# P1_1.net
KiCad netlist of a schematic drawn in Altium Designer
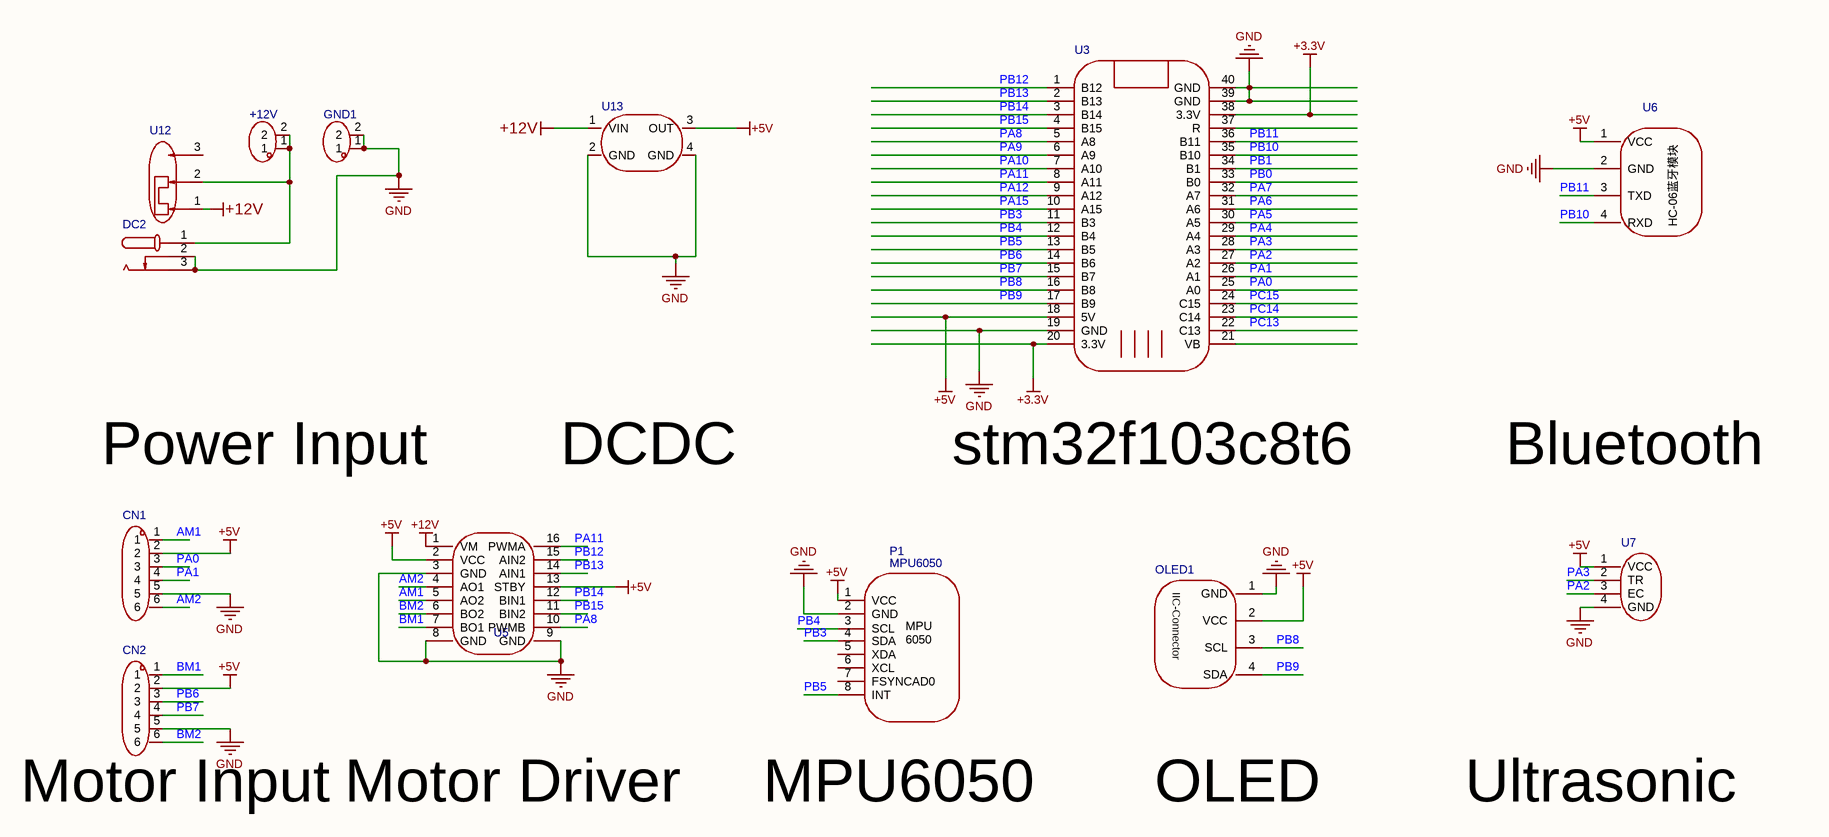
[diagram p0: P1_1.schdoc]

(export (version "E")
  (design (tool "Eeschema 10.0.6"))
  (components
    (comp (ref "+12V")
      (value "~")
      (footprint "HDR-TH_2P-P2.54-V")
      (description "2.54 1*2P 直排针 0.8u镀金 PBT RoHS,针长3*6mm")
      (fields
        (field (name "MANUFACTURER") "Nextron(台湾正凌)")
        (field (name "MANUFACTURERPART") "Z-211-0211-0021-001")
      )
      (libsource (lib "altium-import") (part "root_2_排针2P_"))
    )
    (comp (ref "CN1")
      (value "PH2.0-6P")
      (footprint "PH2.0-6P 直针端子座")
      (fields (field (name "MANUFACTURER") "CAX(创都)") (field (name "MANUFACTURERPART") "PH2.0-4P"))
      (libsource (lib "altium-import") (part "root_0_PH2.0-6P_"))
    )
    (comp (ref "CN2")
      (value "PH2.0-6P")
      (footprint "PH2.0-6P 直针端子座")
      (fields (field (name "MANUFACTURER") "CAX(创都)") (field (name "MANUFACTURERPART") "PH2.0-4P"))
      (libsource (lib "altium-import") (part "root_0_PH2.0-6P_"))
    )
    (comp (ref "DC2")
      (value "~")
      (footprint "DC-IN-TH_KH-DC-005-2.5")
      (description "连接器类型:DC电源插座;安装方式:弯插;触点内径:-;触点外径:6.4mm;额定电流:1A;额定电压:30V;工作温度范围:-25~+70;")
      (fields (field (name "MANUFACTURER") "kinghelm(金航标)") (field (name "MANUFACTURERPART") "KH-DC-005-2.5"))
      (libsource (lib "altium-import") (part "root_0_KH-DC-005-2.5_"))
    )
    (comp (ref "GND1")
      (value "~")
      (footprint "HDR-TH_2P-P2.54-V")
      (description "2.54 1*2P 直排针 0.8u镀金 PBT RoHS,针长3*6mm")
      (fields
        (field (name "MANUFACTURER") "Nextron(台湾正凌)")
        (field (name "MANUFACTURERPART") "Z-211-0211-0021-001")
      )
      (libsource (lib "altium-import") (part "root_2_排针2P_"))
    )
    (comp (ref "OLED1")
      (value "~")
      (footprint "0.96OLED_4P")
      (fields (field (name "MANUFACTURERPART") "0.96OLED_4P_MODULE_JX"))
      (libsource (lib "altium-import") (part "root_0_0.96OLED_4P_"))
    )
    (comp (ref "P1")
      (value "MPU6050")
      (footprint "MPU6050")
      (libsource (lib "altium-import") (part "root_0_MPU6050_"))
    )
    (comp (ref "U3")
      (value "~")
      (footprint "STM32F103C8T6核心板")
      (libsource (lib "altium-import") (part "root_0_stm32f103c8t6最小系统板_"))
    )
    (comp (ref "U5")
      (value "~")
      (footprint "TB6612FNG Module - 8pin x 2")
      (libsource (lib "altium-import") (part "root_0_TB6612FNG模块_"))
    )
    (comp (ref "U6")
      (value "~")
      (footprint "DIP-1X4P2.54（HC-06蓝牙模块）")
      (libsource (lib "altium-import") (part "root_0_蓝牙模块HC-06_"))
    )
    (comp (ref "U7")
      (value "~")
      (footprint "排母-4P")
      (libsource (lib "altium-import") (part "root_0_HC-SR04_1_"))
    )
    (comp (ref "U12")
      (value "SS-12D10-G5")
      (footprint "SW-TH_SS-12D10-G050")
      (description "电路结构:单刀双掷;安装方式:直插;开关颜色:黑色;滑钮形状:矩形柱状;引脚样式:PC引脚;开关长度:12.7mm;开关宽度:6.7mm;开关高度:11.3mm;")
      (fields (field (name "MANUFACTURER") "DEALON(德艺隆)"))
      (libsource (lib "altium-import") (part "root_1_SS-12D10-G5_"))
    )
    (comp (ref "U13")
      (value "~")
      (footprint "MP1584模块")
      (libsource (lib "altium-import") (part "root_0_MP1584模块_"))
    )
  )
  (nets
    (net (code "1") (name "+3.3V") (class "Default")
      (node (ref "U3") (pin "20") (pinfunction "3.3V_20") (pintype "passive"))
      (node (ref "U3") (pin "38") (pinfunction "3.3V_38") (pintype "passive"))
    )
    (net (code "2") (name "+5V") (class "Default")
      (node (ref "CN1") (pin "2") (pinfunction "2_2") (pintype "passive"))
      (node (ref "CN2") (pin "2") (pinfunction "2_2") (pintype "passive"))
      (node (ref "OLED1") (pin "2") (pinfunction "VCC_2") (pintype "passive"))
      (node (ref "P1") (pin "1") (pinfunction "VCC_1") (pintype "passive"))
      (node (ref "U13") (pin "3") (pinfunction "OUT_3") (pintype "passive"))
      (node (ref "U3") (pin "18") (pinfunction "5V_18") (pintype "passive"))
      (node (ref "U5") (pin "13") (pinfunction "STBY_13") (pintype "passive"))
      (node (ref "U5") (pin "2") (pinfunction "VCC_2") (pintype "passive"))
      (node (ref "U6") (pin "1") (pinfunction "VCC_1") (pintype "passive"))
      (node (ref "U7") (pin "1") (pinfunction "VCC_1") (pintype "passive"))
    )
    (net (code "3") (name "+12V") (class "Default")
      (node (ref "U12") (pin "1") (pinfunction "1_1") (pintype "passive"))
      (node (ref "U13") (pin "1") (pinfunction "VIN_1") (pintype "passive"))
      (node (ref "U5") (pin "1") (pinfunction "VM_1") (pintype "passive"))
    )
    (net (code "4") (name "/AM1") (class "Default")
      (node (ref "CN1") (pin "1") (pinfunction "1_1") (pintype "passive"))
      (node (ref "U5") (pin "5") (pinfunction "AO2_5") (pintype "passive"))
    )
    (net (code "5") (name "/AM2") (class "Default")
      (node (ref "CN1") (pin "6") (pinfunction "6_6") (pintype "passive"))
      (node (ref "U5") (pin "4") (pinfunction "AO1_4") (pintype "passive"))
    )
    (net (code "6") (name "/BM1") (class "Default")
      (node (ref "CN2") (pin "1") (pinfunction "1_1") (pintype "passive"))
      (node (ref "U5") (pin "7") (pinfunction "BO1_7") (pintype "passive"))
    )
    (net (code "7") (name "/BM2") (class "Default")
      (node (ref "CN2") (pin "6") (pinfunction "6_6") (pintype "passive"))
      (node (ref "U5") (pin "6") (pinfunction "BO2_6") (pintype "passive"))
    )
    (net (code "8") (name "/PA0") (class "Default")
      (node (ref "CN1") (pin "3") (pinfunction "3_3") (pintype "passive"))
      (node (ref "U3") (pin "25") (pinfunction "A0_25") (pintype "passive"))
    )
    (net (code "9") (name "/PA1") (class "Default")
      (node (ref "CN1") (pin "4") (pinfunction "4_4") (pintype "passive"))
      (node (ref "U3") (pin "26") (pinfunction "A1_26") (pintype "passive"))
    )
    (net (code "10") (name "/PA2") (class "Default")
      (node (ref "U3") (pin "27") (pinfunction "A2_27") (pintype "passive"))
      (node (ref "U7") (pin "3") (pinfunction "EC_3") (pintype "passive"))
    )
    (net (code "11") (name "/PA3") (class "Default")
      (node (ref "U3") (pin "28") (pinfunction "A3_28") (pintype "passive"))
      (node (ref "U7") (pin "2") (pinfunction "TR_2") (pintype "passive"))
    )
    (net (code "12") (name "/PA4") (class "Default")
      (node (ref "U3") (pin "29") (pinfunction "A4_29") (pintype "passive"))
    )
    (net (code "13") (name "/PA5") (class "Default")
      (node (ref "U3") (pin "30") (pinfunction "A5_30") (pintype "passive"))
    )
    (net (code "14") (name "/PA6") (class "Default")
      (node (ref "U3") (pin "31") (pinfunction "A6_31") (pintype "passive"))
    )
    (net (code "15") (name "/PA7") (class "Default")
      (node (ref "U3") (pin "32") (pinfunction "A7_32") (pintype "passive"))
    )
    (net (code "16") (name "/PA8") (class "Default")
      (node (ref "U3") (pin "5") (pinfunction "A8_5") (pintype "passive"))
      (node (ref "U5") (pin "10") (pinfunction "PWMB_10") (pintype "passive"))
    )
    (net (code "17") (name "/PA9") (class "Default")
      (node (ref "U3") (pin "6") (pinfunction "A9_6") (pintype "passive"))
    )
    (net (code "18") (name "/PA10") (class "Default")
      (node (ref "U3") (pin "7") (pinfunction "A10_7") (pintype "passive"))
    )
    (net (code "19") (name "/PA11") (class "Default")
      (node (ref "U3") (pin "8") (pinfunction "A11_8") (pintype "passive"))
      (node (ref "U5") (pin "16") (pinfunction "PWMA_16") (pintype "passive"))
    )
    (net (code "20") (name "/PA12") (class "Default")
      (node (ref "U3") (pin "9") (pinfunction "A12_9") (pintype "passive"))
    )
    (net (code "21") (name "/PA15") (class "Default")
      (node (ref "U3") (pin "10") (pinfunction "A15_10") (pintype "passive"))
    )
    (net (code "22") (name "/PB0") (class "Default")
      (node (ref "U3") (pin "33") (pinfunction "B0_33") (pintype "passive"))
    )
    (net (code "23") (name "/PB1") (class "Default")
      (node (ref "U3") (pin "34") (pinfunction "B1_34") (pintype "passive"))
    )
    (net (code "24") (name "/PB3") (class "Default")
      (node (ref "P1") (pin "4") (pinfunction "SDA_4") (pintype "passive"))
      (node (ref "U3") (pin "11") (pinfunction "B3_11") (pintype "passive"))
    )
    (net (code "25") (name "/PB4") (class "Default")
      (node (ref "P1") (pin "3") (pinfunction "SCL_3") (pintype "passive"))
      (node (ref "U3") (pin "12") (pinfunction "B4_12") (pintype "passive"))
    )
    (net (code "26") (name "/PB5") (class "Default")
      (node (ref "P1") (pin "8") (pinfunction "INT_8") (pintype "passive"))
      (node (ref "U3") (pin "13") (pinfunction "B5_13") (pintype "passive"))
    )
    (net (code "27") (name "/PB6") (class "Default")
      (node (ref "CN2") (pin "3") (pinfunction "3_3") (pintype "passive"))
      (node (ref "U3") (pin "14") (pinfunction "B6_14") (pintype "passive"))
    )
    (net (code "28") (name "/PB7") (class "Default")
      (node (ref "CN2") (pin "4") (pinfunction "4_4") (pintype "passive"))
      (node (ref "U3") (pin "15") (pinfunction "B7_15") (pintype "passive"))
    )
    (net (code "29") (name "/PB8") (class "Default")
      (node (ref "OLED1") (pin "3") (pinfunction "SCL_3") (pintype "passive"))
      (node (ref "U3") (pin "16") (pinfunction "B8_16") (pintype "passive"))
    )
    (net (code "30") (name "/PB9") (class "Default")
      (node (ref "OLED1") (pin "4") (pinfunction "SDA_4") (pintype "passive"))
      (node (ref "U3") (pin "17") (pinfunction "B9_17") (pintype "passive"))
    )
    (net (code "31") (name "/PB10") (class "Default")
      (node (ref "U3") (pin "35") (pinfunction "B10_35") (pintype "passive"))
      (node (ref "U6") (pin "4") (pinfunction "RXD_4") (pintype "passive"))
    )
    (net (code "32") (name "/PB11") (class "Default")
      (node (ref "U3") (pin "36") (pinfunction "B11_36") (pintype "passive"))
      (node (ref "U6") (pin "3") (pinfunction "TXD_3") (pintype "passive"))
    )
    (net (code "33") (name "/PB12") (class "Default")
      (node (ref "U3") (pin "1") (pinfunction "B12_1") (pintype "passive"))
      (node (ref "U5") (pin "15") (pinfunction "AIN2_15") (pintype "passive"))
    )
    (net (code "34") (name "/PB13") (class "Default")
      (node (ref "U3") (pin "2") (pinfunction "B13_2") (pintype "passive"))
      (node (ref "U5") (pin "14") (pinfunction "AIN1_14") (pintype "passive"))
    )
    (net (code "35") (name "/PB14") (class "Default")
      (node (ref "U3") (pin "3") (pinfunction "B14_3") (pintype "passive"))
      (node (ref "U5") (pin "12") (pinfunction "BIN1_12") (pintype "passive"))
    )
    (net (code "36") (name "/PB15") (class "Default")
      (node (ref "U3") (pin "4") (pinfunction "B15_4") (pintype "passive"))
      (node (ref "U5") (pin "11") (pinfunction "BIN2_11") (pintype "passive"))
    )
    (net (code "37") (name "/PC13") (class "Default")
      (node (ref "U3") (pin "22") (pinfunction "C13_22") (pintype "passive"))
    )
    (net (code "38") (name "/PC14") (class "Default")
      (node (ref "U3") (pin "23") (pinfunction "C14_23") (pintype "passive"))
    )
    (net (code "39") (name "/PC15") (class "Default")
      (node (ref "U3") (pin "24") (pinfunction "C15_24") (pintype "passive"))
    )
    (net (code "40") (name "GND") (class "Default")
      (node (ref "CN1") (pin "5") (pinfunction "5_5") (pintype "passive"))
      (node (ref "CN2") (pin "5") (pinfunction "5_5") (pintype "passive"))
      (node (ref "DC2") (pin "2") (pinfunction "2_2") (pintype "passive"))
      (node (ref "DC2") (pin "3") (pinfunction "3_3") (pintype "passive"))
      (node (ref "GND1") (pin "1") (pinfunction "1_1") (pintype "passive"))
      (node (ref "GND1") (pin "2") (pinfunction "2_2") (pintype "passive"))
      (node (ref "OLED1") (pin "1") (pinfunction "GND_1") (pintype "passive"))
      (node (ref "P1") (pin "2") (pinfunction "GND_2") (pintype "passive"))
      (node (ref "U13") (pin "2") (pinfunction "GND_2") (pintype "passive"))
      (node (ref "U13") (pin "4") (pinfunction "GND_4") (pintype "passive"))
      (node (ref "U3") (pin "19") (pinfunction "GND_19") (pintype "passive"))
      (node (ref "U3") (pin "39") (pinfunction "GND_39") (pintype "passive"))
      (node (ref "U3") (pin "40") (pinfunction "GND_40") (pintype "passive"))
      (node (ref "U5") (pin "3") (pinfunction "GND_3") (pintype "passive"))
      (node (ref "U5") (pin "8") (pinfunction "GND_8") (pintype "passive"))
      (node (ref "U5") (pin "9") (pinfunction "GND_9") (pintype "passive"))
      (node (ref "U6") (pin "2") (pinfunction "GND_2") (pintype "passive"))
      (node (ref "U7") (pin "4") (pinfunction "GND_4") (pintype "passive"))
    )
    (net (code "41") (name "Net-(+12V-Pad1)") (class "Default")
      (node (ref "+12V") (pin "1") (pinfunction "1_1") (pintype "passive"))
      (node (ref "+12V") (pin "2") (pinfunction "2_2") (pintype "passive"))
      (node (ref "DC2") (pin "1") (pinfunction "1_1") (pintype "passive"))
      (node (ref "U12") (pin "2") (pinfunction "2_2") (pintype "passive"))
    )
    (net (code "42") (name "unconnected-(P1-FSYNCAD0-Pad7)") (class "Default")
      (node (ref "P1") (pin "7") (pinfunction "FSYNCAD0_7") (pintype "passive"))
    )
    (net (code "43") (name "unconnected-(P1-XCL-Pad6)") (class "Default")
      (node (ref "P1") (pin "6") (pinfunction "XCL_6") (pintype "passive"))
    )
    (net (code "44") (name "unconnected-(P1-XDA-Pad5)") (class "Default")
      (node (ref "P1") (pin "5") (pinfunction "XDA_5") (pintype "passive"))
    )
    (net (code "45") (name "unconnected-(U3-R-Pad37)") (class "Default")
      (node (ref "U3") (pin "37") (pinfunction "R_37") (pintype "passive"))
    )
    (net (code "46") (name "unconnected-(U3-VB-Pad21)") (class "Default")
      (node (ref "U3") (pin "21") (pinfunction "VB_21") (pintype "passive"))
    )
    (net (code "47") (name "unconnected-(U12-Pad3)") (class "Default")
      (node (ref "U12") (pin "3") (pinfunction "3_3") (pintype "passive"))
    )
  )
)
